# UpTo11_MotherBoard.net
KiCad netlist of a schematic drawn in EAGLE
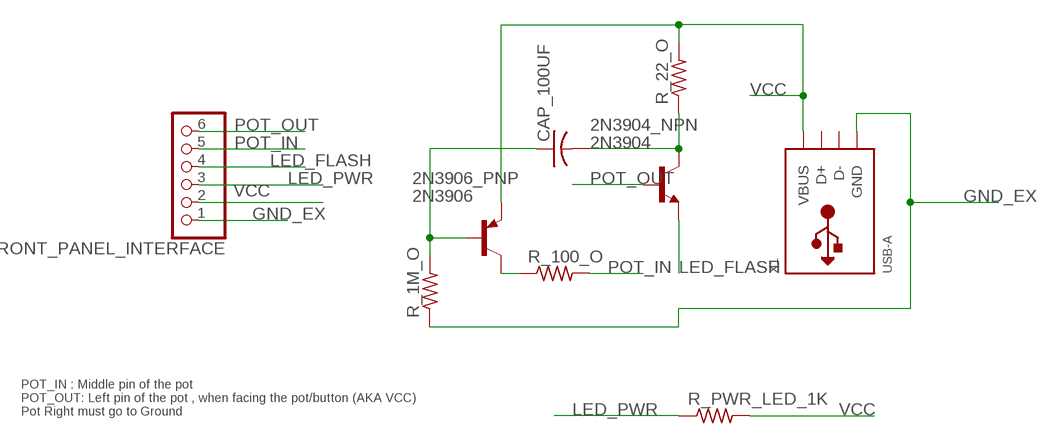
[diagram p0: schematic, sheet 1]

(export (version "E")
  (design (tool "Eeschema 10.0.6"))
  (components
    (comp (ref "2N3904_NPN")
      (value "2N3904")
      (footprint "eagle-import:TO92")
      (libsource (lib "eagle-import") (part "2N3904"))
    )
    (comp (ref "2N3906_PNP")
      (value "2N3906")
      (footprint "eagle-import:TO92")
      (libsource (lib "eagle-import") (part "2N3906"))
    )
    (comp (ref "CAP_100UF")
      (value "C-US025-030X050")
      (footprint "eagle-import:C025-030X050")
      (libsource (lib "eagle-import") (part "C-US025-030X050"))
    )
    (comp (ref "FRONT_PANEL_INTERFACE")
      (value "PINHD-1X6")
      (footprint "eagle-import:1X06")
      (libsource (lib "eagle-import") (part "PINHD-1X6"))
    )
    (comp (ref "R_1M_O")
      (value "R-US_0207/10")
      (footprint "eagle-import:0207_10")
      (libsource (lib "eagle-import") (part "R-US_0207/10"))
    )
    (comp (ref "R_22_O")
      (value "R-US_0207/10")
      (footprint "eagle-import:0207_10")
      (libsource (lib "eagle-import") (part "R-US_0207/10"))
    )
    (comp (ref "R_100_O")
      (value "R-US_0207/10")
      (footprint "eagle-import:0207_10")
      (libsource (lib "eagle-import") (part "R-US_0207/10"))
    )
    (comp (ref "R_PWR_LED_1K")
      (value "R-US_0207/10")
      (footprint "eagle-import:0207_10")
      (libsource (lib "eagle-import") (part "R-US_0207/10"))
    )
    (comp (ref "X1")
      (value "USB-A")
      (footprint "eagle-import:MOLEX_480371000")
      (libsource (lib "eagle-import") (part "USB-A"))
    )
  )
  (nets
    (net (code "1") (name "/GND_EX") (class "Default")
      (node (ref "FRONT_PANEL_INTERFACE") (pin "1") (pinfunction "1_1") (pintype "passive"))
      (node (ref "R_1M_O") (pin "1") (pinfunction "1_1") (pintype "passive"))
      (node (ref "X1") (pin "4") (pinfunction "GND_4") (pintype "power_in"))
    )
    (net (code "2") (name "/LED_FLASH") (class "Default")
      (node (ref "2N3904_NPN") (pin "3") (pinfunction "E_3") (pintype "passive"))
      (node (ref "FRONT_PANEL_INTERFACE") (pin "4") (pinfunction "4_4") (pintype "passive"))
    )
    (net (code "3") (name "/LED_PWR") (class "Default")
      (node (ref "FRONT_PANEL_INTERFACE") (pin "3") (pinfunction "3_3") (pintype "passive"))
      (node (ref "R_PWR_LED_1K") (pin "1") (pinfunction "1_1") (pintype "passive"))
    )
    (net (code "4") (name "/POT_IN") (class "Default")
      (node (ref "FRONT_PANEL_INTERFACE") (pin "5") (pinfunction "5_5") (pintype "passive"))
      (node (ref "R_100_O") (pin "2") (pinfunction "2_2") (pintype "passive"))
    )
    (net (code "5") (name "/POT_OUT") (class "Default")
      (node (ref "2N3904_NPN") (pin "2") (pinfunction "B_2") (pintype "passive"))
      (node (ref "FRONT_PANEL_INTERFACE") (pin "6") (pinfunction "6_6") (pintype "passive"))
    )
    (net (code "6") (name "/VCC") (class "Default")
      (node (ref "2N3906_PNP") (pin "3") (pinfunction "E_3") (pintype "passive"))
      (node (ref "FRONT_PANEL_INTERFACE") (pin "2") (pinfunction "2_2") (pintype "passive"))
      (node (ref "R_22_O") (pin "2") (pinfunction "2_2") (pintype "passive"))
      (node (ref "R_PWR_LED_1K") (pin "2") (pinfunction "2_2") (pintype "passive"))
      (node (ref "X1") (pin "1") (pinfunction "VBUS_1") (pintype "power_in"))
    )
    (net (code "7") (name "Net-(2N3904_NPN-C)") (class "Default")
      (node (ref "2N3904_NPN") (pin "1") (pinfunction "C_1") (pintype "passive"))
      (node (ref "CAP_100UF") (pin "2") (pinfunction "2_2") (pintype "passive"))
      (node (ref "R_22_O") (pin "1") (pinfunction "1_1") (pintype "passive"))
    )
    (net (code "8") (name "Net-(2N3906_PNP-B)") (class "Default")
      (node (ref "2N3906_PNP") (pin "2") (pinfunction "B_2") (pintype "passive"))
      (node (ref "CAP_100UF") (pin "1") (pinfunction "1_1") (pintype "passive"))
      (node (ref "R_1M_O") (pin "2") (pinfunction "2_2") (pintype "passive"))
    )
    (net (code "9") (name "Net-(2N3906_PNP-C)") (class "Default")
      (node (ref "2N3906_PNP") (pin "1") (pinfunction "C_1") (pintype "passive"))
      (node (ref "R_100_O") (pin "1") (pinfunction "1_1") (pintype "passive"))
    )
    (net (code "10") (name "unconnected-(X1-D+-Pad3)") (class "Default")
      (node (ref "X1") (pin "3") (pinfunction "D+_3") (pintype "bidirectional"))
    )
    (net (code "11") (name "unconnected-(X1-D--Pad2)") (class "Default")
      (node (ref "X1") (pin "2") (pinfunction "D-_2") (pintype "bidirectional"))
    )
  )
)
